# 4ChannelADCs.net
KiCad netlist of a schematic drawn in Altium Designer
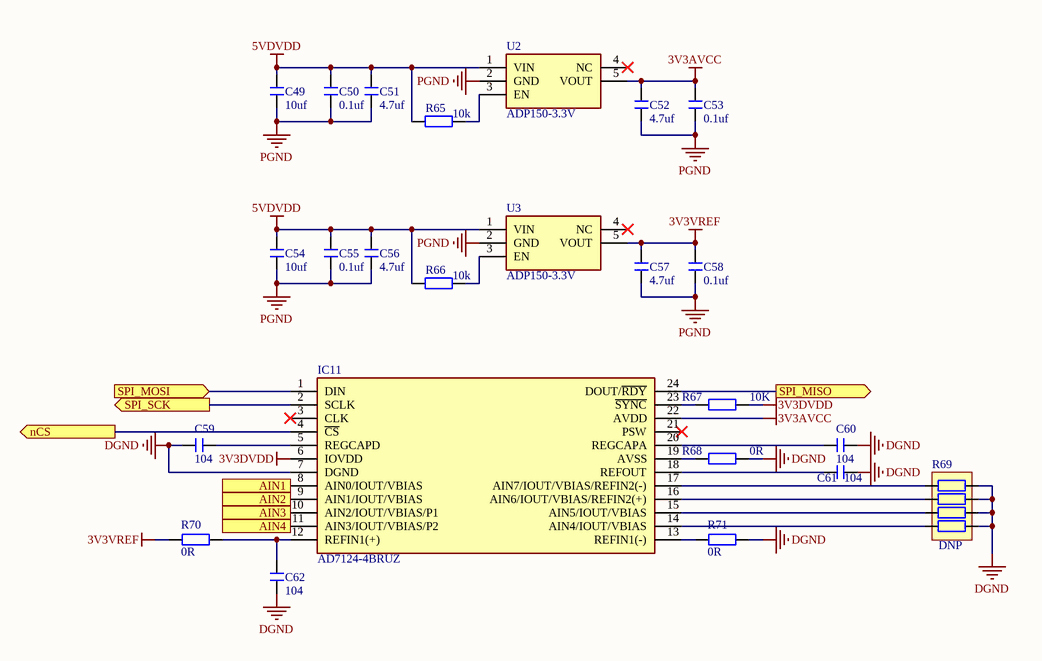
[diagram p0: 4ChannelADCs.SchDoc]

(export (version "E")
  (design (tool "Eeschema 10.0.6"))
  (components
    (comp (ref "C49")
      (value "10uf")
      (footprint "C 0805_L")
      (description "贴片电容")
      (libsource (lib "0.1 - 电阻-电容-电感") (part "C"))
    )
    (comp (ref "C50")
      (value "0.1uf")
      (footprint "C 0805_L")
      (description "贴片电容")
      (libsource (lib "0.1 - 电阻-电容-电感") (part "C"))
    )
    (comp (ref "C51")
      (value "4.7uf")
      (footprint "C 0805_L")
      (description "贴片电容")
      (libsource (lib "0.1 - 电阻-电容-电感") (part "C"))
    )
    (comp (ref "C52")
      (value "4.7uf")
      (footprint "C 0805_L")
      (description "贴片电容")
      (libsource (lib "0.1 - 电阻-电容-电感") (part "C"))
    )
    (comp (ref "C53")
      (value "0.1uf")
      (footprint "C 0805_L")
      (description "贴片电容")
      (libsource (lib "0.1 - 电阻-电容-电感") (part "C"))
    )
    (comp (ref "C54")
      (value "10uf")
      (footprint "C 0805_L")
      (description "贴片电容")
      (libsource (lib "0.1 - 电阻-电容-电感") (part "C"))
    )
    (comp (ref "C55")
      (value "0.1uf")
      (footprint "C 0805_L")
      (description "贴片电容")
      (libsource (lib "0.1 - 电阻-电容-电感") (part "C"))
    )
    (comp (ref "C56")
      (value "4.7uf")
      (footprint "C 0805_L")
      (description "贴片电容")
      (libsource (lib "0.1 - 电阻-电容-电感") (part "C"))
    )
    (comp (ref "C57")
      (value "4.7uf")
      (footprint "C 0805_L")
      (description "贴片电容")
      (libsource (lib "0.1 - 电阻-电容-电感") (part "C"))
    )
    (comp (ref "C58")
      (value "0.1uf")
      (footprint "C 0805_L")
      (description "贴片电容")
      (libsource (lib "0.1 - 电阻-电容-电感") (part "C"))
    )
    (comp (ref "C59")
      (value "104")
      (footprint "C 0603_L")
      (description "贴片电容")
      (libsource (lib "0.1 - 电阻-电容-电感") (part "C"))
    )
    (comp (ref "C60")
      (value "104")
      (footprint "C 0603_L")
      (description "贴片电容")
      (libsource (lib "0.1 - 电阻-电容-电感") (part "C"))
    )
    (comp (ref "C61")
      (value "104")
      (footprint "C 0603_L")
      (description "贴片电容")
      (libsource (lib "0.1 - 电阻-电容-电感") (part "C"))
    )
    (comp (ref "C62")
      (value "104")
      (footprint "C 0603_L")
      (description "贴片电容")
      (libsource (lib "0.1 - 电阻-电容-电感") (part "C"))
    )
    (comp (ref "IC11")
      (value "AD7124-4BRUZ")
      (footprint "SkylakeADPcbLib:SOP65P640X120-24N")
      (description "Integrated Circuit")
      (fields (field (name "MOUSER PART NUMBER") "584-AD7124-4BRUZ"))
      (libsource (lib "*") (part "AD7124-4BRUZ"))
    )
    (comp (ref "R65")
      (value "10k")
      (footprint "0805_R")
      (description "贴片电阻 0805 电阻")
      (libsource (lib "逍遥封装库") (part "0805 电阻"))
    )
    (comp (ref "R66")
      (value "10k")
      (footprint "0805_R")
      (description "贴片电阻 0805 电阻")
      (libsource (lib "逍遥封装库") (part "0805 电阻"))
    )
    (comp (ref "R67")
      (value "10K")
      (footprint "R 0603_L")
      (description "贴片电阻")
      (libsource (lib "0.1 - 电阻-电容-电感") (part "R"))
    )
    (comp (ref "R68")
      (value "0R")
      (footprint "R 0603_L")
      (description "贴片电阻")
      (libsource (lib "0.1 - 电阻-电容-电感") (part "R"))
    )
    (comp (ref "R69")
      (value "DNP")
      (footprint "RCA-8P4R-0603")
      (description "贴片排阻")
      (libsource (lib "0.1 - 电阻-电容-电感") (part "R-8P4R"))
    )
    (comp (ref "R70")
      (value "0R")
      (footprint "R 0603_L")
      (description "贴片电阻")
      (libsource (lib "0.1 - 电阻-电容-电感") (part "R"))
    )
    (comp (ref "R71")
      (value "0R")
      (footprint "R 0603_L")
      (description "贴片电阻")
      (libsource (lib "0.1 - 电阻-电容-电感") (part "R"))
    )
    (comp (ref "U2")
      (value "ADP150-3.3V")
      (description "IOVDD needs 1.8V")
      (libsource (lib "CN0383") (part "ADP150"))
    )
    (comp (ref "U3")
      (value "ADP150-3.3V")
      (description "IOVDD needs 1.8V")
      (libsource (lib "CN0383") (part "ADP150"))
    )
  )
  (nets
    (net (code "1") (name "/AIN1") (class "Default")
      (node (ref "IC11") (pin "8") (pinfunction "AIN0/IOUT/VBIAS_8") (pintype "passive"))
    )
    (net (code "2") (name "/AIN2") (class "Default")
      (node (ref "IC11") (pin "9") (pinfunction "AIN1/IOUT/VBIAS_9") (pintype "passive"))
    )
    (net (code "3") (name "/AIN3") (class "Default")
      (node (ref "IC11") (pin "10") (pinfunction "AIN2/IOUT/VBIAS/P1_10") (pintype "passive"))
    )
    (net (code "4") (name "/AIN4") (class "Default")
      (node (ref "IC11") (pin "11") (pinfunction "AIN3/IOUT/VBIAS/P2_11") (pintype "passive"))
    )
    (net (code "5") (name "/SPI_MISO") (class "Default")
      (node (ref "IC11") (pin "24") (pinfunction "DOUT/~{RDY}_24") (pintype "passive"))
    )
    (net (code "6") (name "/SPI_MOSI") (class "Default")
      (node (ref "IC11") (pin "1") (pinfunction "DIN_1") (pintype "passive"))
    )
    (net (code "7") (name "/SPI_SCK") (class "Default")
      (node (ref "IC11") (pin "2") (pinfunction "SCLK_2") (pintype "passive"))
    )
    (net (code "8") (name "/nCS") (class "Default")
      (node (ref "IC11") (pin "4") (pinfunction "~{CS}_4") (pintype "passive"))
    )
    (net (code "9") (name "3V3AVCC") (class "Default")
      (node (ref "C52") (pin "2") (pinfunction "2_2") (pintype "passive"))
      (node (ref "C53") (pin "2") (pinfunction "2_2") (pintype "passive"))
      (node (ref "IC11") (pin "22") (pinfunction "AVDD_22") (pintype "passive"))
      (node (ref "U2") (pin "5") (pinfunction "VOUT_5") (pintype "passive"))
    )
    (net (code "10") (name "3V3DVDD") (class "Default")
      (node (ref "IC11") (pin "6") (pinfunction "IOVDD_6") (pintype "passive"))
      (node (ref "R67") (pin "1") (pinfunction "1_1") (pintype "passive"))
    )
    (net (code "11") (name "3V3VREF") (class "Default")
      (node (ref "C57") (pin "2") (pinfunction "2_2") (pintype "passive"))
      (node (ref "C58") (pin "2") (pinfunction "2_2") (pintype "passive"))
      (node (ref "R70") (pin "2") (pinfunction "2_2") (pintype "passive"))
      (node (ref "U3") (pin "5") (pinfunction "VOUT_5") (pintype "passive"))
    )
    (net (code "12") (name "5VDVDD") (class "Default")
      (node (ref "C49") (pin "2") (pinfunction "2_2") (pintype "passive"))
      (node (ref "C50") (pin "2") (pinfunction "2_2") (pintype "passive"))
      (node (ref "C51") (pin "2") (pinfunction "2_2") (pintype "passive"))
      (node (ref "C54") (pin "2") (pinfunction "2_2") (pintype "passive"))
      (node (ref "C55") (pin "2") (pinfunction "2_2") (pintype "passive"))
      (node (ref "C56") (pin "2") (pinfunction "2_2") (pintype "passive"))
      (node (ref "R65") (pin "1") (pinfunction "1_1") (pintype "passive"))
      (node (ref "R66") (pin "1") (pinfunction "1_1") (pintype "passive"))
      (node (ref "U2") (pin "1") (pinfunction "VIN_1") (pintype "passive"))
      (node (ref "U3") (pin "1") (pinfunction "VIN_1") (pintype "passive"))
    )
    (net (code "13") (name "DGND") (class "Default")
      (node (ref "C59") (pin "1") (pinfunction "1_1") (pintype "passive"))
      (node (ref "C60") (pin "1") (pinfunction "1_1") (pintype "passive"))
      (node (ref "C61") (pin "1") (pinfunction "1_1") (pintype "passive"))
      (node (ref "C62") (pin "1") (pinfunction "1_1") (pintype "passive"))
      (node (ref "IC11") (pin "7") (pinfunction "DGND_7") (pintype "passive"))
      (node (ref "R68") (pin "1") (pinfunction "1_1") (pintype "passive"))
      (node (ref "R69") (pin "5") (pinfunction "5_5") (pintype "passive"))
      (node (ref "R69") (pin "6") (pinfunction "6_6") (pintype "passive"))
      (node (ref "R69") (pin "7") (pinfunction "7_7") (pintype "passive"))
      (node (ref "R69") (pin "8") (pinfunction "8_8") (pintype "passive"))
      (node (ref "R71") (pin "1") (pinfunction "1_1") (pintype "passive"))
    )
    (net (code "14") (name "Net-(IC11-AIN4{slash}IOUT{slash}VBIAS)") (class "Default")
      (node (ref "IC11") (pin "14") (pinfunction "AIN4/IOUT/VBIAS_14") (pintype "passive"))
      (node (ref "R69") (pin "4") (pinfunction "4_4") (pintype "passive"))
    )
    (net (code "15") (name "Net-(IC11-AIN5{slash}IOUT{slash}VBIAS)") (class "Default")
      (node (ref "IC11") (pin "15") (pinfunction "AIN5/IOUT/VBIAS_15") (pintype "passive"))
      (node (ref "R69") (pin "3") (pinfunction "3_3") (pintype "passive"))
    )
    (net (code "16") (name "Net-(IC11-AIN6{slash}IOUT{slash}VBIAS{slash}REFIN2(+))") (class "Default")
      (node (ref "IC11") (pin "16") (pinfunction "AIN6/IOUT/VBIAS/REFIN2(+)_16") (pintype "passive"))
      (node (ref "R69") (pin "2") (pinfunction "2_2") (pintype "passive"))
    )
    (net (code "17") (name "Net-(IC11-AIN7{slash}IOUT{slash}VBIAS{slash}REFIN2(-))") (class "Default")
      (node (ref "IC11") (pin "17") (pinfunction "AIN7/IOUT/VBIAS/REFIN2(-)_17") (pintype "passive"))
      (node (ref "R69") (pin "1") (pinfunction "1_1") (pintype "passive"))
    )
    (net (code "18") (name "Net-(IC11-AVSS)") (class "Default")
      (node (ref "IC11") (pin "19") (pinfunction "AVSS_19") (pintype "passive"))
      (node (ref "R68") (pin "2") (pinfunction "2_2") (pintype "passive"))
    )
    (net (code "19") (name "Net-(IC11-REFIN1(+))") (class "Default")
      (node (ref "C62") (pin "2") (pinfunction "2_2") (pintype "passive"))
      (node (ref "IC11") (pin "12") (pinfunction "REFIN1(+)_12") (pintype "passive"))
      (node (ref "R70") (pin "1") (pinfunction "1_1") (pintype "passive"))
    )
    (net (code "20") (name "Net-(IC11-REFIN1(-))") (class "Default")
      (node (ref "IC11") (pin "13") (pinfunction "REFIN1(-)_13") (pintype "passive"))
      (node (ref "R71") (pin "2") (pinfunction "2_2") (pintype "passive"))
    )
    (net (code "21") (name "Net-(IC11-REFOUT)") (class "Default")
      (node (ref "C61") (pin "2") (pinfunction "2_2") (pintype "passive"))
      (node (ref "IC11") (pin "18") (pinfunction "REFOUT_18") (pintype "passive"))
    )
    (net (code "22") (name "Net-(IC11-REGCAPA)") (class "Default")
      (node (ref "C60") (pin "2") (pinfunction "2_2") (pintype "passive"))
      (node (ref "IC11") (pin "20") (pinfunction "REGCAPA_20") (pintype "passive"))
    )
    (net (code "23") (name "Net-(IC11-REGCAPD)") (class "Default")
      (node (ref "C59") (pin "2") (pinfunction "2_2") (pintype "passive"))
      (node (ref "IC11") (pin "5") (pinfunction "REGCAPD_5") (pintype "passive"))
    )
    (net (code "24") (name "Net-(IC11-~{SYNC})") (class "Default")
      (node (ref "IC11") (pin "23") (pinfunction "~{SYNC}_23") (pintype "passive"))
      (node (ref "R67") (pin "2") (pinfunction "2_2") (pintype "passive"))
    )
    (net (code "25") (name "Net-(U2-EN)") (class "Default")
      (node (ref "R65") (pin "2") (pinfunction "2_2") (pintype "passive"))
      (node (ref "U2") (pin "3") (pinfunction "EN_3") (pintype "passive"))
    )
    (net (code "26") (name "Net-(U3-EN)") (class "Default")
      (node (ref "R66") (pin "2") (pinfunction "2_2") (pintype "passive"))
      (node (ref "U3") (pin "3") (pinfunction "EN_3") (pintype "passive"))
    )
    (net (code "27") (name "PGND") (class "Default")
      (node (ref "C49") (pin "1") (pinfunction "1_1") (pintype "passive"))
      (node (ref "C50") (pin "1") (pinfunction "1_1") (pintype "passive"))
      (node (ref "C51") (pin "1") (pinfunction "1_1") (pintype "passive"))
      (node (ref "C52") (pin "1") (pinfunction "1_1") (pintype "passive"))
      (node (ref "C53") (pin "1") (pinfunction "1_1") (pintype "passive"))
      (node (ref "C54") (pin "1") (pinfunction "1_1") (pintype "passive"))
      (node (ref "C55") (pin "1") (pinfunction "1_1") (pintype "passive"))
      (node (ref "C56") (pin "1") (pinfunction "1_1") (pintype "passive"))
      (node (ref "C57") (pin "1") (pinfunction "1_1") (pintype "passive"))
      (node (ref "C58") (pin "1") (pinfunction "1_1") (pintype "passive"))
      (node (ref "U2") (pin "2") (pinfunction "GND_2") (pintype "passive"))
      (node (ref "U3") (pin "2") (pinfunction "GND_2") (pintype "passive"))
    )
    (net (code "28") (name "unconnected-(IC11-CLK-Pad3)") (class "Default")
      (node (ref "IC11") (pin "3") (pinfunction "CLK_3") (pintype "passive+no_connect"))
    )
    (net (code "29") (name "unconnected-(IC11-PSW-Pad21)") (class "Default")
      (node (ref "IC11") (pin "21") (pinfunction "PSW_21") (pintype "passive+no_connect"))
    )
    (net (code "30") (name "unconnected-(U2-NC-Pad4)") (class "Default")
      (node (ref "U2") (pin "4") (pinfunction "NC_4") (pintype "passive+no_connect"))
    )
    (net (code "31") (name "unconnected-(U3-NC-Pad4)") (class "Default")
      (node (ref "U3") (pin "4") (pinfunction "NC_4") (pintype "passive+no_connect"))
    )
  )
)
